# 6502_connection.net
KiCad netlist of a schematic drawn in Altium Designer
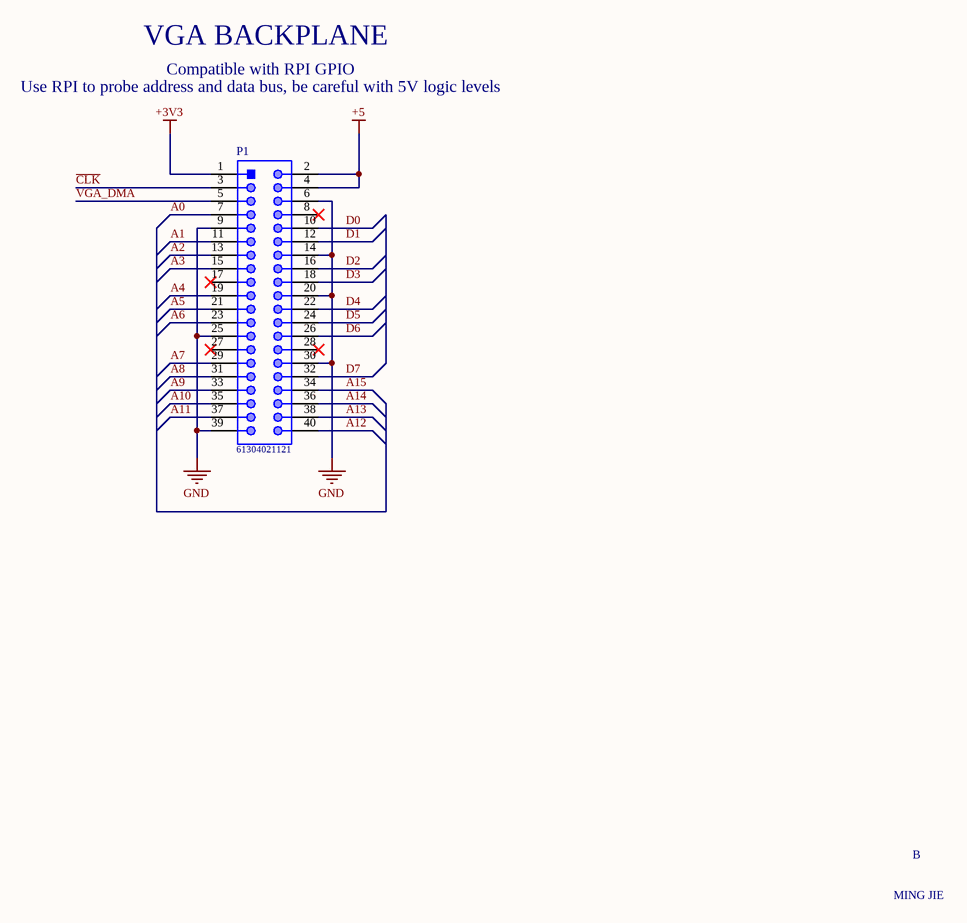
[diagram p0: 6502_connection.SchDoc]

(export (version "E")
  (design (tool "Eeschema 10.0.6"))
  (components
    (comp (ref "P1")
      (value "61304021121")
      (footprint "61304021121")
      (description "THT Vertical Pin Header WR-PHD, Pitch 2.54 mm, Dual Row, 40 pins")
      (fields (field (name "MANUFACTURER") "Wurth Elektronik") (field (name "PUBLISHER") "WurthElektronik"))
      (libsource (lib "Altium Content Vault") (part "WE-CN-2P-M-R40"))
    )
  )
  (nets
    (net (code "1") (name "+3V3") (class "Default")
      (node (ref "P1") (pin "1") (pinfunction "1_1") (pintype "passive"))
    )
    (net (code "2") (name "+5") (class "Default")
      (node (ref "P1") (pin "2") (pinfunction "2_2") (pintype "passive"))
      (node (ref "P1") (pin "4") (pinfunction "4_4") (pintype "passive"))
    )
    (net (code "3") (name "/A0") (class "Default")
      (node (ref "P1") (pin "7") (pinfunction "7_7") (pintype "passive"))
    )
    (net (code "4") (name "/A1") (class "Default")
      (node (ref "P1") (pin "11") (pinfunction "11_11") (pintype "passive"))
    )
    (net (code "5") (name "/A2") (class "Default")
      (node (ref "P1") (pin "13") (pinfunction "13_13") (pintype "passive"))
    )
    (net (code "6") (name "/A3") (class "Default")
      (node (ref "P1") (pin "15") (pinfunction "15_15") (pintype "passive"))
    )
    (net (code "7") (name "/A4") (class "Default")
      (node (ref "P1") (pin "19") (pinfunction "19_19") (pintype "passive"))
    )
    (net (code "8") (name "/A5") (class "Default")
      (node (ref "P1") (pin "21") (pinfunction "21_21") (pintype "passive"))
    )
    (net (code "9") (name "/A6") (class "Default")
      (node (ref "P1") (pin "23") (pinfunction "23_23") (pintype "passive"))
    )
    (net (code "10") (name "/A7") (class "Default")
      (node (ref "P1") (pin "29") (pinfunction "29_29") (pintype "passive"))
    )
    (net (code "11") (name "/A8") (class "Default")
      (node (ref "P1") (pin "31") (pinfunction "31_31") (pintype "passive"))
    )
    (net (code "12") (name "/A9") (class "Default")
      (node (ref "P1") (pin "33") (pinfunction "33_33") (pintype "passive"))
    )
    (net (code "13") (name "/A10") (class "Default")
      (node (ref "P1") (pin "35") (pinfunction "35_35") (pintype "passive"))
    )
    (net (code "14") (name "/A11") (class "Default")
      (node (ref "P1") (pin "37") (pinfunction "37_37") (pintype "passive"))
    )
    (net (code "15") (name "/A12") (class "Default")
      (node (ref "P1") (pin "40") (pinfunction "40_40") (pintype "passive"))
    )
    (net (code "16") (name "/A13") (class "Default")
      (node (ref "P1") (pin "38") (pinfunction "38_38") (pintype "passive"))
    )
    (net (code "17") (name "/A14") (class "Default")
      (node (ref "P1") (pin "36") (pinfunction "36_36") (pintype "passive"))
    )
    (net (code "18") (name "/A15") (class "Default")
      (node (ref "P1") (pin "34") (pinfunction "34_34") (pintype "passive"))
    )
    (net (code "19") (name "/D0") (class "Default")
      (node (ref "P1") (pin "10") (pinfunction "10_10") (pintype "passive"))
    )
    (net (code "20") (name "/D1") (class "Default")
      (node (ref "P1") (pin "12") (pinfunction "12_12") (pintype "passive"))
    )
    (net (code "21") (name "/D2") (class "Default")
      (node (ref "P1") (pin "16") (pinfunction "16_16") (pintype "passive"))
    )
    (net (code "22") (name "/D3") (class "Default")
      (node (ref "P1") (pin "18") (pinfunction "18_18") (pintype "passive"))
    )
    (net (code "23") (name "/D4") (class "Default")
      (node (ref "P1") (pin "22") (pinfunction "22_22") (pintype "passive"))
    )
    (net (code "24") (name "/D5") (class "Default")
      (node (ref "P1") (pin "24") (pinfunction "24_24") (pintype "passive"))
    )
    (net (code "25") (name "/D6") (class "Default")
      (node (ref "P1") (pin "26") (pinfunction "26_26") (pintype "passive"))
    )
    (net (code "26") (name "/D7") (class "Default")
      (node (ref "P1") (pin "32") (pinfunction "32_32") (pintype "passive"))
    )
    (net (code "27") (name "/VGA_~{DMA}") (class "Default")
      (node (ref "P1") (pin "5") (pinfunction "5_5") (pintype "passive"))
    )
    (net (code "28") (name "/~{CLK}") (class "Default")
      (node (ref "P1") (pin "3") (pinfunction "3_3") (pintype "passive"))
    )
    (net (code "29") (name "GND") (class "Default")
      (node (ref "P1") (pin "14") (pinfunction "14_14") (pintype "passive"))
      (node (ref "P1") (pin "20") (pinfunction "20_20") (pintype "passive"))
      (node (ref "P1") (pin "25") (pinfunction "25_25") (pintype "passive"))
      (node (ref "P1") (pin "30") (pinfunction "30_30") (pintype "passive"))
      (node (ref "P1") (pin "39") (pinfunction "39_39") (pintype "passive"))
      (node (ref "P1") (pin "6") (pinfunction "6_6") (pintype "passive"))
      (node (ref "P1") (pin "9") (pinfunction "9_9") (pintype "passive"))
    )
    (net (code "30") (name "unconnected-(P1-Pad8)") (class "Default")
      (node (ref "P1") (pin "8") (pinfunction "8_8") (pintype "passive+no_connect"))
    )
    (net (code "31") (name "unconnected-(P1-Pad17)") (class "Default")
      (node (ref "P1") (pin "17") (pinfunction "17_17") (pintype "passive+no_connect"))
    )
    (net (code "32") (name "unconnected-(P1-Pad27)") (class "Default")
      (node (ref "P1") (pin "27") (pinfunction "27_27") (pintype "passive+no_connect"))
    )
    (net (code "33") (name "unconnected-(P1-Pad28)") (class "Default")
      (node (ref "P1") (pin "28") (pinfunction "28_28") (pintype "passive+no_connect"))
    )
  )
)
